# Power.net
KiCad netlist of a schematic drawn in Altium Designer
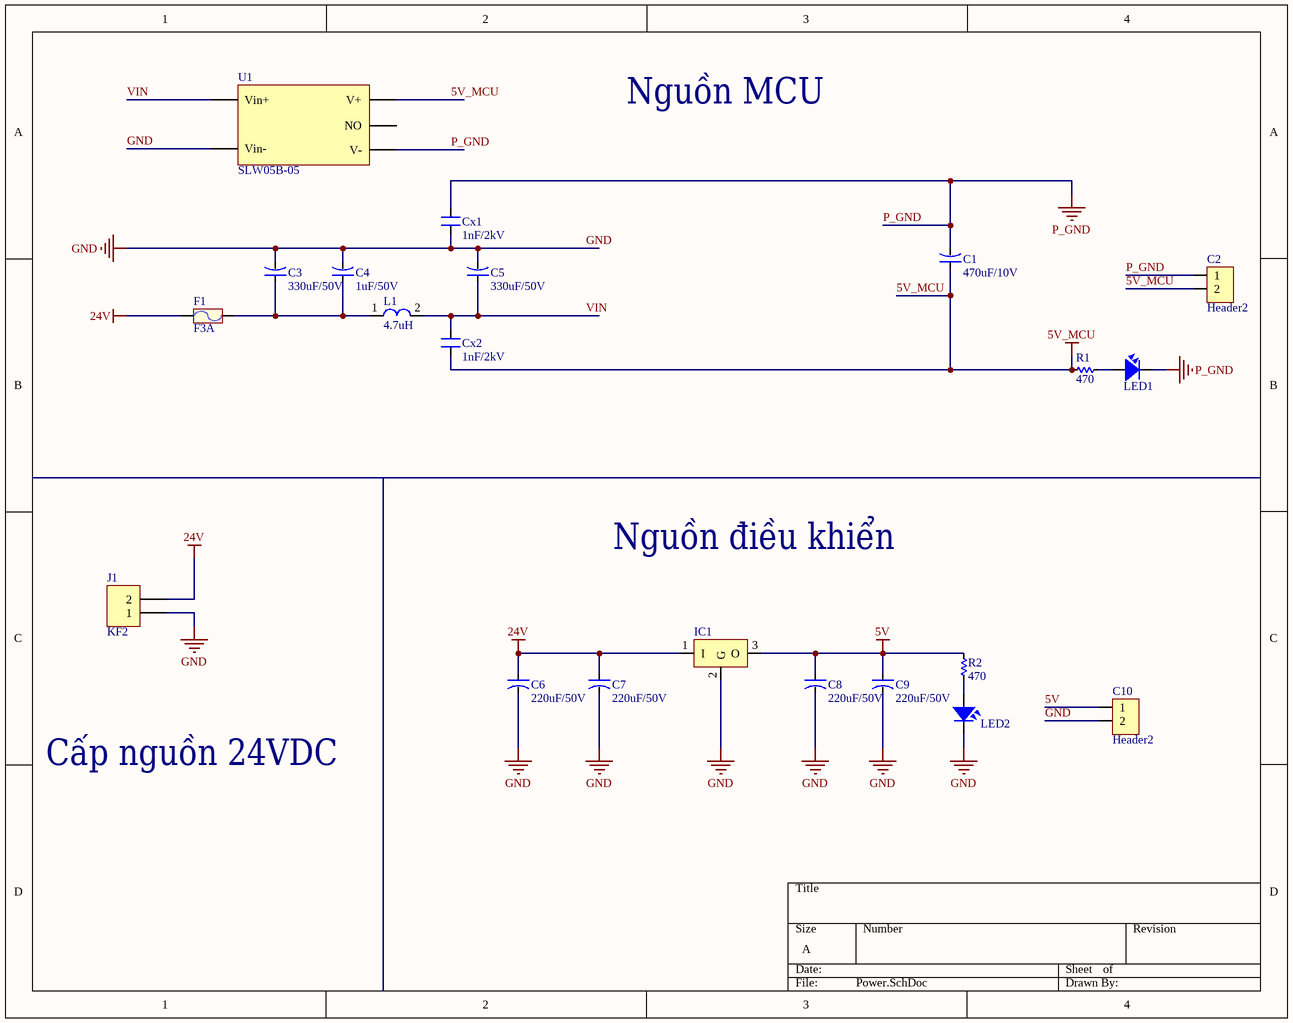
[diagram p0: Power.SchDoc]

(export (version "E")
  (design (tool "Eeschema 10.0.6"))
  (components
    (comp (ref "C1")
      (value "470uF/10V")
      (footprint "TANTALUM-7343")
      (description "http://linhkienchatluong.vn/tu-tantalium/tu-tantalum-7343-477a-10v-470uf-73x43mm_sp460_ct1168.aspx")
      (libsource (lib "LIBRARY") (part "CN-TANTALUM-SMD"))
    )
    (comp (ref "C2")
      (value "Header2")
      (footprint "Header2")
      (fields
        (field (name "MANUFACTURER") "Würth Elektronik eiSos GmbH")
        (field (name "PARTNO") "613002143121")
        (field (name "CREATED BY") "Karrer Zheng")
      )
      (libsource (lib "LIBRARY") (part "Header2"))
    )
    (comp (ref "C3")
      (value "330uF/50V")
      (footprint "CAP-ALU-SMD-G")
      (description "http://linhkienchatluong.vn/tu-nhom---tu-hoa-dan/tu-nhom-50v-330uf-10x102mm_sp455_ct2883.aspx")
      (fields (field (name "PUBLISHER") "Altium Limited"))
      (libsource (lib "LIBRARY") (part "CN-ALU-SMD"))
    )
    (comp (ref "C4")
      (value "1uF/50V")
      (footprint "CAP-ALU-SMD-4.5x5x1.4")
      (description "http://linhkienchatluong.vn/tu-nhom---tu-hoa-dan/tu-nhom-50v-1uf-4x55mm_sp455_ct981.aspx")
      (fields (field (name "PUBLISHER") "Altium Limited"))
      (libsource (lib "LIBRARY") (part "CN-ALU-SMD"))
    )
    (comp (ref "C5")
      (value "330uF/50V")
      (footprint "CAP-ALU-SMD-G")
      (description "Polarized Capacitor (Axial)")
      (fields (field (name "PUBLISHER") "Altium Limited"))
      (libsource (lib "LIBRARY") (part "CN-ALU-SMD"))
    )
    (comp (ref "C6")
      (value "220uF/50V")
      (footprint "CAP-ALU-SMD-6.3x7.7x2.2")
      (description "Polarized Capacitor (Axial)")
      (fields (field (name "PUBLISHER") "Altium Limited"))
      (libsource (lib "LIBRARY") (part "CN-ALU-SMD"))
    )
    (comp (ref "C7")
      (value "220uF/50V")
      (footprint "CAP-ALU-SMD-6.3x7.7x2.2")
      (description "Polarized Capacitor (Axial)")
      (fields (field (name "PUBLISHER") "Altium Limited"))
      (libsource (lib "LIBRARY") (part "CN-ALU-SMD"))
    )
    (comp (ref "C8")
      (value "220uF/50V")
      (footprint "CAP-ALU-SMD-6.3x7.7x2.2")
      (description "http://linhkienchatluong.vn/tu-nhom---tu-hoa-dan/tu-nhom-16v-220uf-63x77mm_sp455_ct964.aspx")
      (fields (field (name "PUBLISHER") "Altium Limited"))
      (libsource (lib "LIBRARY") (part "CN-ALU-SMD"))
    )
    (comp (ref "C9")
      (value "220uF/50V")
      (footprint "CAP-ALU-SMD-6.3x7.7x2.2")
      (description "Polarized Capacitor (Axial)")
      (fields (field (name "PUBLISHER") "Altium Limited"))
      (libsource (lib "LIBRARY") (part "CN-ALU-SMD"))
    )
    (comp (ref "C10")
      (value "Header2")
      (footprint "Header2")
      (description "Header IDC, 2 x 1 Pin Vertical 2.54mm Pitch (Non-Boxed, Male)")
      (fields
        (field (name "MANUFACTURER") "Würth Elektronik eiSos GmbH")
        (field (name "PARTNO") "613002143121")
        (field (name "CREATED BY") "Karrer Zheng")
      )
      (libsource (lib "LIBRARY") (part "Header2"))
    )
    (comp (ref "Cx1") (value "1nF/2kV") (footprint "CN2-B") (libsource (lib "LIBRARY") (part "CN")))
    (comp (ref "Cx2") (value "1nF/2kV") (footprint "CN2-B") (libsource (lib "LIBRARY") (part "CN")))
    (comp (ref "F1")
      (value "F3A")
      (footprint "FUSE_SMD 1812")
      (fields (field (name "DESIGNED BY") "VanDungEvn"))
      (libsource (lib "LIBRARY") (part "Fuse"))
    )
    (comp (ref "IC1")
      (value "LM7805")
      (footprint "TO252-123")
      (fields (field (name "PUBLISHER") "Altium Limited"))
      (libsource (lib "LIBRARY") (part "LM78xx"))
    )
    (comp (ref "J1")
      (value "KF2")
      (footprint "KF2-7.62")
      (fields
        (field (name "MANUFACTURER") "Würth Elektronik eiSos GmbH")
        (field (name "PARTNO") "691103110002")
        (field (name "CREATED BY") "Karrer Zheng")
      )
      (libsource (lib "LIBRARY") (part "KF2"))
    )
    (comp (ref "L1")
      (value "4.7uH")
      (footprint "L-SMD-M-12x10")
      (fields
        (field (name "PARTNO") "78477010")
        (field (name "MANUFACTURER") "Wurth Elektronik")
        (field (name "CREATED BY") "Baojun Chen")
      )
      (libsource (lib "LIBRARY") (part "L-SMD-1"))
    )
    (comp (ref "LED1") (value "LED") (footprint "LED-1206-Red") (libsource (lib "LIBRARY") (part "LED SMD")))
    (comp (ref "LED2") (value "LED") (footprint "LED-1206-Red") (libsource (lib "LIBRARY") (part "LED SMD")))
    (comp (ref "R1")
      (value "470")
      (footprint "RES-SMD-0805")
      (description "Resistor")
      (fields
        (field (name "MANUFACTURER") "Generic Components")
        (field (name "PUBLISHER") "Altium Hobart Technology Centre")
      )
      (libsource (lib "LIBRARY") (part "Res-SMD"))
    )
    (comp (ref "R2")
      (value "470")
      (footprint "RES-SMD-0805")
      (description "Resistor")
      (fields
        (field (name "MANUFACTURER") "Generic Components")
        (field (name "PUBLISHER") "Altium Hobart Technology Centre")
      )
      (libsource (lib "LIBRARY") (part "Res-SMD"))
    )
    (comp (ref "U1")
      (value "SLW05B-05")
      (footprint "SLW05B-05")
      (libsource (lib "LIBRARY") (part "Module DC-DC 220/5V/5W"))
    )
  )
  (nets
    (net (code "1") (name "/VIN") (class "Default")
      (node (ref "C5") (pin "1") (pinfunction "1_1") (pintype "passive"))
      (node (ref "Cx2") (pin "2") (pinfunction "2_2") (pintype "passive"))
      (node (ref "L1") (pin "2") (pinfunction "2_2") (pintype "passive"))
      (node (ref "U1") (pin "Vin+") (pinfunction "Vin+_Vin+") (pintype "passive"))
    )
    (net (code "2") (name "5V") (class "Default")
      (node (ref "C10") (pin "1") (pinfunction "1_1") (pintype "passive"))
      (node (ref "C8") (pin "1") (pinfunction "1_1") (pintype "passive"))
      (node (ref "C9") (pin "1") (pinfunction "1_1") (pintype "passive"))
      (node (ref "IC1") (pin "3") (pinfunction "O_3") (pintype "power_in"))
      (node (ref "R2") (pin "1") (pinfunction "1_1") (pintype "passive"))
    )
    (net (code "3") (name "5V_MCU") (class "Default")
      (node (ref "C1") (pin "1") (pinfunction "1_1") (pintype "passive"))
      (node (ref "C2") (pin "2") (pinfunction "2_2") (pintype "passive"))
      (node (ref "Cx2") (pin "1") (pinfunction "1_1") (pintype "passive"))
      (node (ref "R1") (pin "1") (pinfunction "1_1") (pintype "passive"))
      (node (ref "U1") (pin "V+") (pinfunction "V+_V+") (pintype "passive"))
    )
    (net (code "4") (name "24V") (class "Default")
      (node (ref "C6") (pin "1") (pinfunction "1_1") (pintype "passive"))
      (node (ref "C7") (pin "1") (pinfunction "1_1") (pintype "passive"))
      (node (ref "F1") (pin "1") (pinfunction "1_1") (pintype "passive"))
      (node (ref "IC1") (pin "1") (pinfunction "I_1") (pintype "power_in"))
      (node (ref "J1") (pin "2") (pinfunction "2_2") (pintype "passive"))
    )
    (net (code "5") (name "GND") (class "Default")
      (node (ref "C10") (pin "2") (pinfunction "2_2") (pintype "passive"))
      (node (ref "C3") (pin "2") (pinfunction "2_2") (pintype "passive"))
      (node (ref "C4") (pin "2") (pinfunction "2_2") (pintype "passive"))
      (node (ref "C5") (pin "2") (pinfunction "2_2") (pintype "passive"))
      (node (ref "C6") (pin "2") (pinfunction "2_2") (pintype "passive"))
      (node (ref "C7") (pin "2") (pinfunction "2_2") (pintype "passive"))
      (node (ref "C8") (pin "2") (pinfunction "2_2") (pintype "passive"))
      (node (ref "C9") (pin "2") (pinfunction "2_2") (pintype "passive"))
      (node (ref "Cx1") (pin "1") (pinfunction "1_1") (pintype "passive"))
      (node (ref "IC1") (pin "2") (pinfunction "G_2") (pintype "power_in"))
      (node (ref "J1") (pin "1") (pinfunction "1_1") (pintype "passive"))
      (node (ref "LED2") (pin "2") (pinfunction "2_2") (pintype "passive"))
      (node (ref "U1") (pin "Vin-") (pinfunction "Vin-_Vin-") (pintype "passive"))
    )
    (net (code "6") (name "Net-(C3-Pad1)") (class "Default")
      (node (ref "C3") (pin "1") (pinfunction "1_1") (pintype "passive"))
      (node (ref "C4") (pin "1") (pinfunction "1_1") (pintype "passive"))
      (node (ref "F1") (pin "2") (pinfunction "2_2") (pintype "passive"))
      (node (ref "L1") (pin "1") (pinfunction "1_1") (pintype "passive"))
    )
    (net (code "7") (name "Net-(LED1-Pad1)") (class "Default")
      (node (ref "LED1") (pin "1") (pinfunction "1_1") (pintype "passive"))
      (node (ref "R1") (pin "2") (pinfunction "2_2") (pintype "passive"))
    )
    (net (code "8") (name "Net-(LED2-Pad1)") (class "Default")
      (node (ref "LED2") (pin "1") (pinfunction "1_1") (pintype "passive"))
      (node (ref "R2") (pin "2") (pinfunction "2_2") (pintype "passive"))
    )
    (net (code "9") (name "P_GND") (class "Default")
      (node (ref "C1") (pin "2") (pinfunction "2_2") (pintype "passive"))
      (node (ref "C2") (pin "1") (pinfunction "1_1") (pintype "passive"))
      (node (ref "Cx1") (pin "2") (pinfunction "2_2") (pintype "passive"))
      (node (ref "LED1") (pin "2") (pinfunction "2_2") (pintype "passive"))
      (node (ref "U1") (pin "V-") (pinfunction "V-_V-") (pintype "passive"))
    )
    (net (code "10") (name "unconnected-(U1-PadNO)") (class "Default")
      (node (ref "U1") (pin "NO") (pinfunction "NO_NO") (pintype "passive"))
    )
  )
)
